# microfono_v1_rev0.net
KiCad netlist of a schematic drawn in EAGLE
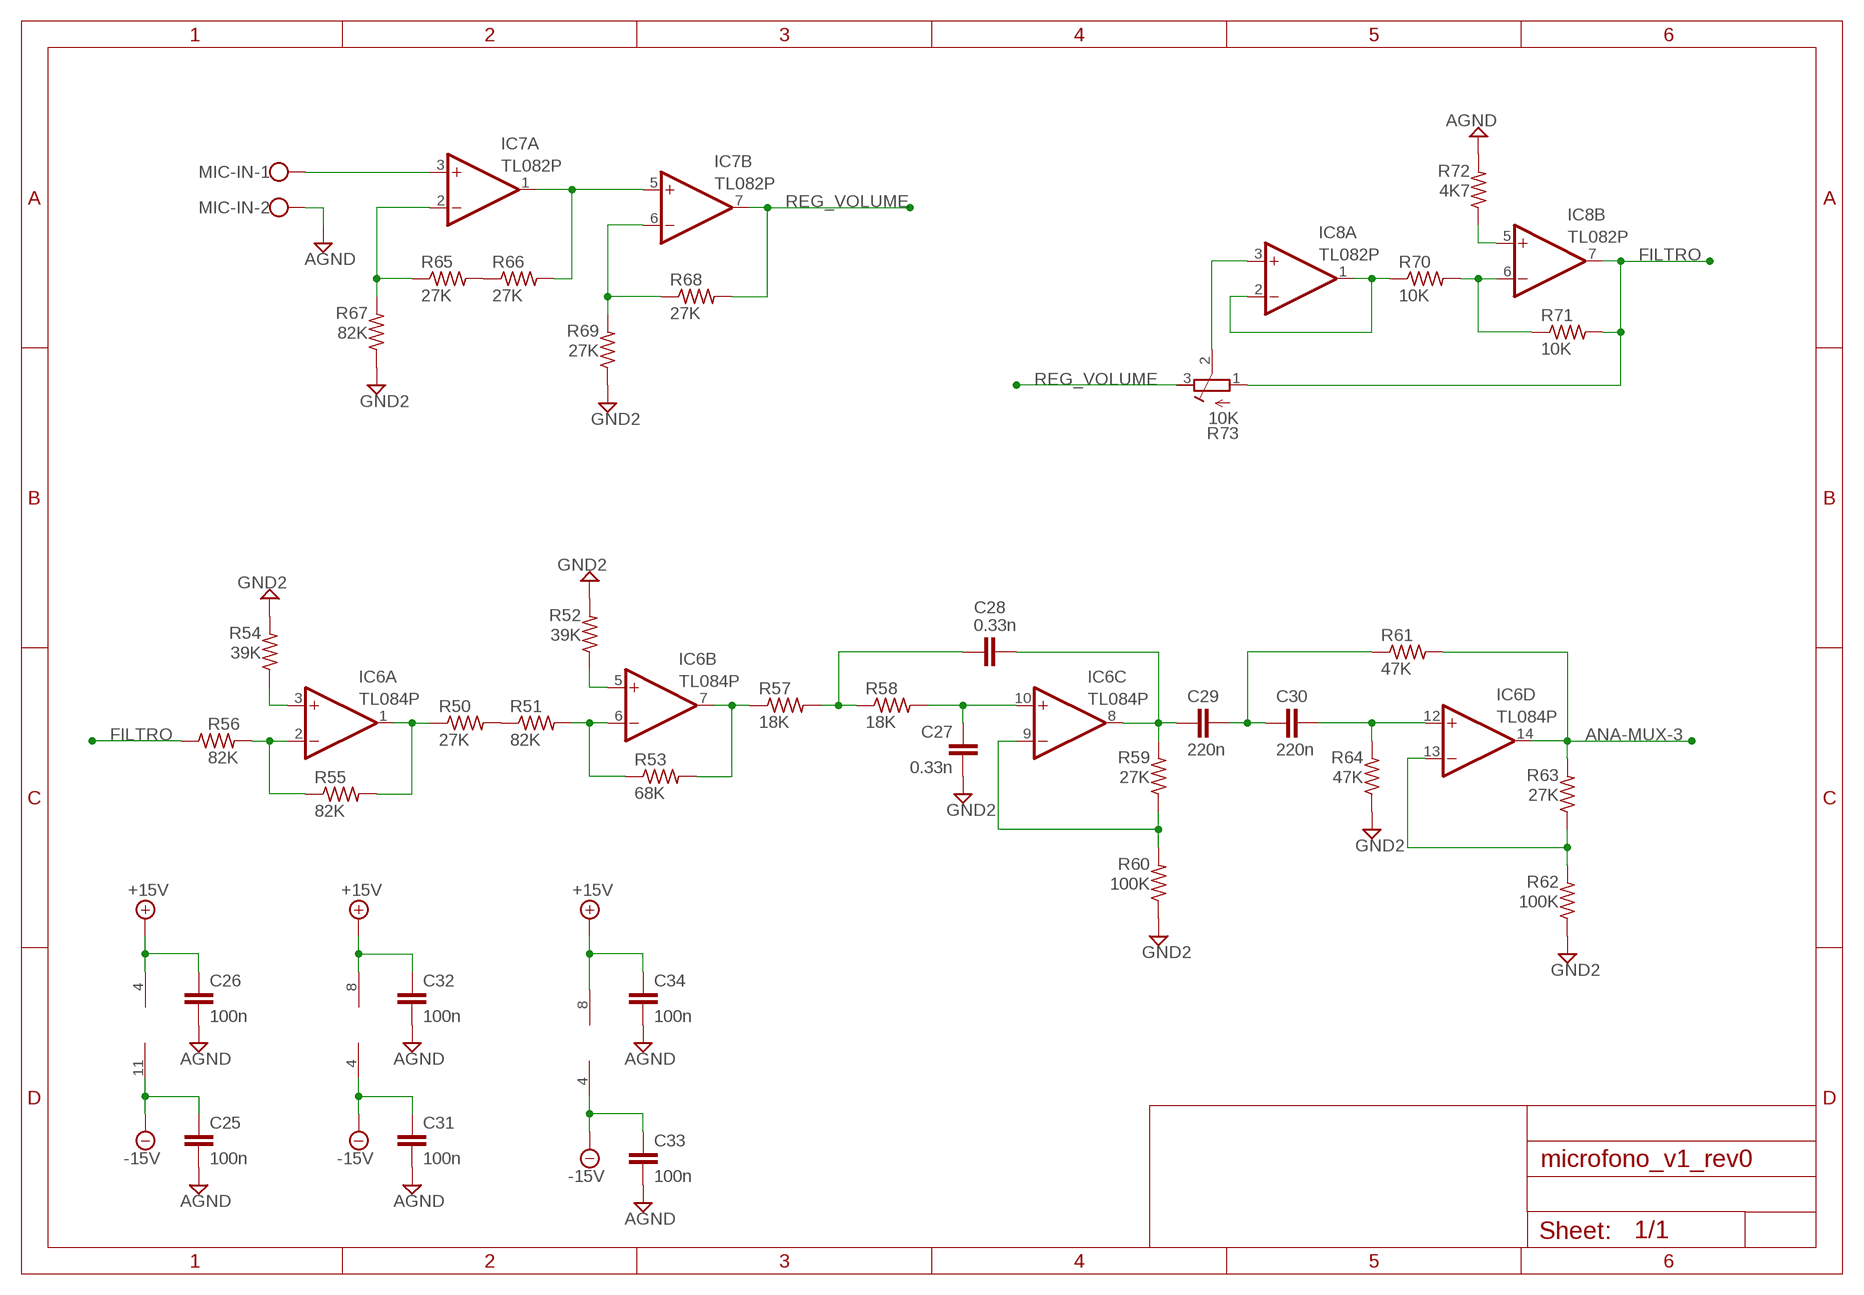
[diagram p0: schematic, sheet 1]

(export (version "E")
  (design (tool "Eeschema 10.0.6"))
  (components
    (comp (ref "C25")
      (value "100n")
      (footprint "eagle-import:C025-025X050")
      (libsource (lib "eagle-import") (part "C-EU025-025X050"))
    )
    (comp (ref "C26")
      (value "100n")
      (footprint "eagle-import:C025-025X050")
      (libsource (lib "eagle-import") (part "C-EU025-025X050"))
    )
    (comp (ref "C27")
      (value "0.33n")
      (footprint "eagle-import:C025-025X050")
      (libsource (lib "eagle-import") (part "C-EU025-025X050"))
    )
    (comp (ref "C28")
      (value "0.33n")
      (footprint "eagle-import:C025-025X050")
      (libsource (lib "eagle-import") (part "C-EU025-025X050"))
    )
    (comp (ref "C29")
      (value "220n")
      (footprint "eagle-import:C025-025X050")
      (libsource (lib "eagle-import") (part "C-EU025-025X050"))
    )
    (comp (ref "C30")
      (value "220n")
      (footprint "eagle-import:C025-025X050")
      (libsource (lib "eagle-import") (part "C-EU025-025X050"))
    )
    (comp (ref "C31")
      (value "100n")
      (footprint "eagle-import:C025-025X050")
      (libsource (lib "eagle-import") (part "C-EU025-025X050"))
    )
    (comp (ref "C32")
      (value "100n")
      (footprint "eagle-import:C025-025X050")
      (libsource (lib "eagle-import") (part "C-EU025-025X050"))
    )
    (comp (ref "C33")
      (value "100n")
      (footprint "eagle-import:C025-025X050")
      (libsource (lib "eagle-import") (part "C-EU025-025X050"))
    )
    (comp (ref "C34")
      (value "100n")
      (footprint "eagle-import:C025-025X050")
      (libsource (lib "eagle-import") (part "C-EU025-025X050"))
    )
    (comp (ref "IC6")
      (value "TL084P")
      (footprint "eagle-import:DIL14")
      (libsource (lib "eagle-import") (part "TL084P"))
    )
    (comp (ref "IC7")
      (value "TL082P")
      (footprint "eagle-import:DIL08")
      (libsource (lib "eagle-import") (part "TL082P"))
    )
    (comp (ref "IC8")
      (value "TL082P")
      (footprint "eagle-import:DIL08")
      (libsource (lib "eagle-import") (part "TL082P"))
    )
    (comp (ref "MIC-IN")
      (value "W237-102")
      (footprint "eagle-import:W237-102")
      (fields (field (name "MPN") "237-102"))
      (libsource (lib "eagle-import") (part "W237-102"))
    )
    (comp (ref "R50")
      (value "27K")
      (footprint "eagle-import:0204_7")
      (libsource (lib "eagle-import") (part "R-US_0204/7"))
    )
    (comp (ref "R51")
      (value "82K")
      (footprint "eagle-import:0204_7")
      (libsource (lib "eagle-import") (part "R-US_0204/7"))
    )
    (comp (ref "R52")
      (value "39K")
      (footprint "eagle-import:0204_7")
      (libsource (lib "eagle-import") (part "R-US_0204/7"))
    )
    (comp (ref "R53")
      (value "68K")
      (footprint "eagle-import:0204_7")
      (libsource (lib "eagle-import") (part "R-US_0204/7"))
    )
    (comp (ref "R54")
      (value "39K")
      (footprint "eagle-import:0204_7")
      (libsource (lib "eagle-import") (part "R-US_0204/7"))
    )
    (comp (ref "R55")
      (value "82K")
      (footprint "eagle-import:0204_7")
      (libsource (lib "eagle-import") (part "R-US_0204/7"))
    )
    (comp (ref "R56")
      (value "82K")
      (footprint "eagle-import:0204_7")
      (libsource (lib "eagle-import") (part "R-US_0204/7"))
    )
    (comp (ref "R57")
      (value "18K")
      (footprint "eagle-import:0204_7")
      (libsource (lib "eagle-import") (part "R-US_0204/7"))
    )
    (comp (ref "R58")
      (value "18K")
      (footprint "eagle-import:0204_7")
      (libsource (lib "eagle-import") (part "R-US_0204/7"))
    )
    (comp (ref "R59")
      (value "27K")
      (footprint "eagle-import:0204_7")
      (libsource (lib "eagle-import") (part "R-US_0204/7"))
    )
    (comp (ref "R60")
      (value "100K")
      (footprint "eagle-import:0204_7")
      (libsource (lib "eagle-import") (part "R-US_0204/7"))
    )
    (comp (ref "R61")
      (value "47K")
      (footprint "eagle-import:0204_7")
      (libsource (lib "eagle-import") (part "R-US_0204/7"))
    )
    (comp (ref "R62")
      (value "100K")
      (footprint "eagle-import:0204_7")
      (libsource (lib "eagle-import") (part "R-US_0204/7"))
    )
    (comp (ref "R63")
      (value "27K")
      (footprint "eagle-import:0204_7")
      (libsource (lib "eagle-import") (part "R-US_0204/7"))
    )
    (comp (ref "R64")
      (value "47K")
      (footprint "eagle-import:0204_7")
      (libsource (lib "eagle-import") (part "R-US_0204/7"))
    )
    (comp (ref "R65")
      (value "27K")
      (footprint "eagle-import:0204_7")
      (libsource (lib "eagle-import") (part "R-US_0204/7"))
    )
    (comp (ref "R66")
      (value "27K")
      (footprint "eagle-import:0204_7")
      (libsource (lib "eagle-import") (part "R-US_0204/7"))
    )
    (comp (ref "R67")
      (value "82K")
      (footprint "eagle-import:0204_7")
      (libsource (lib "eagle-import") (part "R-US_0204/7"))
    )
    (comp (ref "R68")
      (value "27K")
      (footprint "eagle-import:0204_7")
      (libsource (lib "eagle-import") (part "R-US_0204/7"))
    )
    (comp (ref "R69")
      (value "27K")
      (footprint "eagle-import:0204_7")
      (libsource (lib "eagle-import") (part "R-US_0204/7"))
    )
    (comp (ref "R70")
      (value "10K")
      (footprint "eagle-import:0204_7")
      (libsource (lib "eagle-import") (part "R-US_0204/7"))
    )
    (comp (ref "R71")
      (value "10K")
      (footprint "eagle-import:0204_7")
      (libsource (lib "eagle-import") (part "R-US_0204/7"))
    )
    (comp (ref "R72")
      (value "4K7")
      (footprint "eagle-import:0204_7")
      (libsource (lib "eagle-import") (part "R-US_0204/7"))
    )
    (comp (ref "R73")
      (value "10K")
      (footprint "eagle-import:RTRIM64W")
      (libsource (lib "eagle-import") (part "R-TRIMM64W"))
    )
  )
  (nets
    (net (code "1") (name "+15V") (class "Default")
      (node (ref "C26") (pin "1") (pinfunction "1_1") (pintype "passive"))
      (node (ref "C32") (pin "1") (pinfunction "1_1") (pintype "passive"))
      (node (ref "C34") (pin "1") (pinfunction "1_1") (pintype "passive"))
      (node (ref "IC6") (pin "4") (pinfunction "V+_4") (pintype "power_in"))
      (node (ref "IC7") (pin "8") (pinfunction "V+_8") (pintype "power_in"))
      (node (ref "IC8") (pin "8") (pinfunction "V+_8") (pintype "power_in"))
    )
    (net (code "2") (name "-15V") (class "Default")
      (node (ref "C25") (pin "1") (pinfunction "1_1") (pintype "passive"))
      (node (ref "C31") (pin "1") (pinfunction "1_1") (pintype "passive"))
      (node (ref "C33") (pin "1") (pinfunction "1_1") (pintype "passive"))
      (node (ref "IC6") (pin "11") (pinfunction "V-_11") (pintype "power_in"))
      (node (ref "IC7") (pin "4") (pinfunction "V-_4") (pintype "power_in"))
      (node (ref "IC8") (pin "4") (pinfunction "V-_4") (pintype "power_in"))
    )
    (net (code "3") (name "/ANA-MUX-3") (class "Default")
      (node (ref "IC6") (pin "14") (pinfunction "OUT_14") (pintype "output"))
      (node (ref "R61") (pin "2") (pinfunction "2_2") (pintype "passive"))
      (node (ref "R63") (pin "2") (pinfunction "2_2") (pintype "passive"))
    )
    (net (code "4") (name "/FILTRO") (class "Default")
      (node (ref "IC8") (pin "7") (pinfunction "OUT_7") (pintype "output"))
      (node (ref "R56") (pin "1") (pinfunction "1_1") (pintype "passive"))
      (node (ref "R71") (pin "2") (pinfunction "2_2") (pintype "passive"))
      (node (ref "R73") (pin "1") (pinfunction "A_1") (pintype "passive"))
    )
    (net (code "5") (name "/REG_VOLUME") (class "Default")
      (node (ref "IC7") (pin "7") (pinfunction "OUT_7") (pintype "output"))
      (node (ref "R68") (pin "2") (pinfunction "2_2") (pintype "passive"))
      (node (ref "R73") (pin "3") (pinfunction "E_3") (pintype "passive"))
    )
    (net (code "6") (name "AGND") (class "Default")
      (node (ref "C25") (pin "2") (pinfunction "2_2") (pintype "passive"))
      (node (ref "C26") (pin "2") (pinfunction "2_2") (pintype "passive"))
      (node (ref "C31") (pin "2") (pinfunction "2_2") (pintype "passive"))
      (node (ref "C32") (pin "2") (pinfunction "2_2") (pintype "passive"))
      (node (ref "C33") (pin "2") (pinfunction "2_2") (pintype "passive"))
      (node (ref "C34") (pin "2") (pinfunction "2_2") (pintype "passive"))
      (node (ref "MIC-IN") (pin "2") (pinfunction "KL_2") (pintype "passive"))
      (node (ref "R72") (pin "2") (pinfunction "2_2") (pintype "passive"))
    )
    (net (code "7") (name "GND2") (class "Default")
      (node (ref "C27") (pin "2") (pinfunction "2_2") (pintype "passive"))
      (node (ref "R52") (pin "2") (pinfunction "2_2") (pintype "passive"))
      (node (ref "R54") (pin "2") (pinfunction "2_2") (pintype "passive"))
      (node (ref "R60") (pin "1") (pinfunction "1_1") (pintype "passive"))
      (node (ref "R62") (pin "1") (pinfunction "1_1") (pintype "passive"))
      (node (ref "R64") (pin "1") (pinfunction "1_1") (pintype "passive"))
      (node (ref "R67") (pin "1") (pinfunction "1_1") (pintype "passive"))
      (node (ref "R69") (pin "1") (pinfunction "1_1") (pintype "passive"))
    )
    (net (code "8") (name "Net-(C28-Pad1)") (class "Default")
      (node (ref "C28") (pin "1") (pinfunction "1_1") (pintype "passive"))
      (node (ref "R57") (pin "2") (pinfunction "2_2") (pintype "passive"))
      (node (ref "R58") (pin "1") (pinfunction "1_1") (pintype "passive"))
    )
    (net (code "9") (name "Net-(C29-Pad2)") (class "Default")
      (node (ref "C29") (pin "2") (pinfunction "2_2") (pintype "passive"))
      (node (ref "C30") (pin "1") (pinfunction "1_1") (pintype "passive"))
      (node (ref "R61") (pin "1") (pinfunction "1_1") (pintype "passive"))
    )
    (net (code "10") (name "Net-(IC6A-+IN)") (class "Default")
      (node (ref "IC6") (pin "3") (pinfunction "+IN_3") (pintype "input"))
      (node (ref "R54") (pin "1") (pinfunction "1_1") (pintype "passive"))
    )
    (net (code "11") (name "Net-(IC6A--IN)") (class "Default")
      (node (ref "IC6") (pin "2") (pinfunction "-IN_2") (pintype "input"))
      (node (ref "R55") (pin "1") (pinfunction "1_1") (pintype "passive"))
      (node (ref "R56") (pin "2") (pinfunction "2_2") (pintype "passive"))
    )
    (net (code "12") (name "Net-(IC6A-OUT)") (class "Default")
      (node (ref "IC6") (pin "1") (pinfunction "OUT_1") (pintype "output"))
      (node (ref "R50") (pin "1") (pinfunction "1_1") (pintype "passive"))
      (node (ref "R55") (pin "2") (pinfunction "2_2") (pintype "passive"))
    )
    (net (code "13") (name "Net-(IC6B-+IN)") (class "Default")
      (node (ref "IC6") (pin "5") (pinfunction "+IN_5") (pintype "input"))
      (node (ref "R52") (pin "1") (pinfunction "1_1") (pintype "passive"))
    )
    (net (code "14") (name "Net-(IC6B--IN)") (class "Default")
      (node (ref "IC6") (pin "6") (pinfunction "-IN_6") (pintype "input"))
      (node (ref "R51") (pin "2") (pinfunction "2_2") (pintype "passive"))
      (node (ref "R53") (pin "1") (pinfunction "1_1") (pintype "passive"))
    )
    (net (code "15") (name "Net-(IC6B-OUT)") (class "Default")
      (node (ref "IC6") (pin "7") (pinfunction "OUT_7") (pintype "output"))
      (node (ref "R53") (pin "2") (pinfunction "2_2") (pintype "passive"))
      (node (ref "R57") (pin "1") (pinfunction "1_1") (pintype "passive"))
    )
    (net (code "16") (name "Net-(IC6C-+IN)") (class "Default")
      (node (ref "C27") (pin "1") (pinfunction "1_1") (pintype "passive"))
      (node (ref "IC6") (pin "10") (pinfunction "+IN_10") (pintype "input"))
      (node (ref "R58") (pin "2") (pinfunction "2_2") (pintype "passive"))
    )
    (net (code "17") (name "Net-(IC6C--IN)") (class "Default")
      (node (ref "IC6") (pin "9") (pinfunction "-IN_9") (pintype "input"))
      (node (ref "R59") (pin "1") (pinfunction "1_1") (pintype "passive"))
      (node (ref "R60") (pin "2") (pinfunction "2_2") (pintype "passive"))
    )
    (net (code "18") (name "Net-(IC6C-OUT)") (class "Default")
      (node (ref "C28") (pin "2") (pinfunction "2_2") (pintype "passive"))
      (node (ref "C29") (pin "1") (pinfunction "1_1") (pintype "passive"))
      (node (ref "IC6") (pin "8") (pinfunction "OUT_8") (pintype "output"))
      (node (ref "R59") (pin "2") (pinfunction "2_2") (pintype "passive"))
    )
    (net (code "19") (name "Net-(IC6D-+IN)") (class "Default")
      (node (ref "C30") (pin "2") (pinfunction "2_2") (pintype "passive"))
      (node (ref "IC6") (pin "12") (pinfunction "+IN_12") (pintype "input"))
      (node (ref "R64") (pin "2") (pinfunction "2_2") (pintype "passive"))
    )
    (net (code "20") (name "Net-(IC6D--IN)") (class "Default")
      (node (ref "IC6") (pin "13") (pinfunction "-IN_13") (pintype "input"))
      (node (ref "R62") (pin "2") (pinfunction "2_2") (pintype "passive"))
      (node (ref "R63") (pin "1") (pinfunction "1_1") (pintype "passive"))
    )
    (net (code "21") (name "Net-(IC7A-+IN)") (class "Default")
      (node (ref "IC7") (pin "3") (pinfunction "+IN_3") (pintype "input"))
      (node (ref "MIC-IN") (pin "1") (pinfunction "KL_1") (pintype "passive"))
    )
    (net (code "22") (name "Net-(IC7A--IN)") (class "Default")
      (node (ref "IC7") (pin "2") (pinfunction "-IN_2") (pintype "input"))
      (node (ref "R65") (pin "1") (pinfunction "1_1") (pintype "passive"))
      (node (ref "R67") (pin "2") (pinfunction "2_2") (pintype "passive"))
    )
    (net (code "23") (name "Net-(IC7A-OUT)") (class "Default")
      (node (ref "IC7") (pin "1") (pinfunction "OUT_1") (pintype "output"))
      (node (ref "IC7") (pin "5") (pinfunction "+IN_5") (pintype "input"))
      (node (ref "R66") (pin "2") (pinfunction "2_2") (pintype "passive"))
    )
    (net (code "24") (name "Net-(IC7B--IN)") (class "Default")
      (node (ref "IC7") (pin "6") (pinfunction "-IN_6") (pintype "input"))
      (node (ref "R68") (pin "1") (pinfunction "1_1") (pintype "passive"))
      (node (ref "R69") (pin "2") (pinfunction "2_2") (pintype "passive"))
    )
    (net (code "25") (name "Net-(IC8A-+IN)") (class "Default")
      (node (ref "IC8") (pin "3") (pinfunction "+IN_3") (pintype "input"))
      (node (ref "R73") (pin "2") (pinfunction "S_2") (pintype "passive"))
    )
    (net (code "26") (name "Net-(IC8A--IN)") (class "Default")
      (node (ref "IC8") (pin "1") (pinfunction "OUT_1") (pintype "output"))
      (node (ref "IC8") (pin "2") (pinfunction "-IN_2") (pintype "input"))
      (node (ref "R70") (pin "1") (pinfunction "1_1") (pintype "passive"))
    )
    (net (code "27") (name "Net-(IC8B-+IN)") (class "Default")
      (node (ref "IC8") (pin "5") (pinfunction "+IN_5") (pintype "input"))
      (node (ref "R72") (pin "1") (pinfunction "1_1") (pintype "passive"))
    )
    (net (code "28") (name "Net-(IC8B--IN)") (class "Default")
      (node (ref "IC8") (pin "6") (pinfunction "-IN_6") (pintype "input"))
      (node (ref "R70") (pin "2") (pinfunction "2_2") (pintype "passive"))
      (node (ref "R71") (pin "1") (pinfunction "1_1") (pintype "passive"))
    )
    (net (code "29") (name "Net-(R50-Pad2)") (class "Default")
      (node (ref "R50") (pin "2") (pinfunction "2_2") (pintype "passive"))
      (node (ref "R51") (pin "1") (pinfunction "1_1") (pintype "passive"))
    )
    (net (code "30") (name "Net-(R65-Pad2)") (class "Default")
      (node (ref "R65") (pin "2") (pinfunction "2_2") (pintype "passive"))
      (node (ref "R66") (pin "1") (pinfunction "1_1") (pintype "passive"))
    )
  )
)
